# buffer.net
KiCad netlist of a schematic drawn in Altium Designer
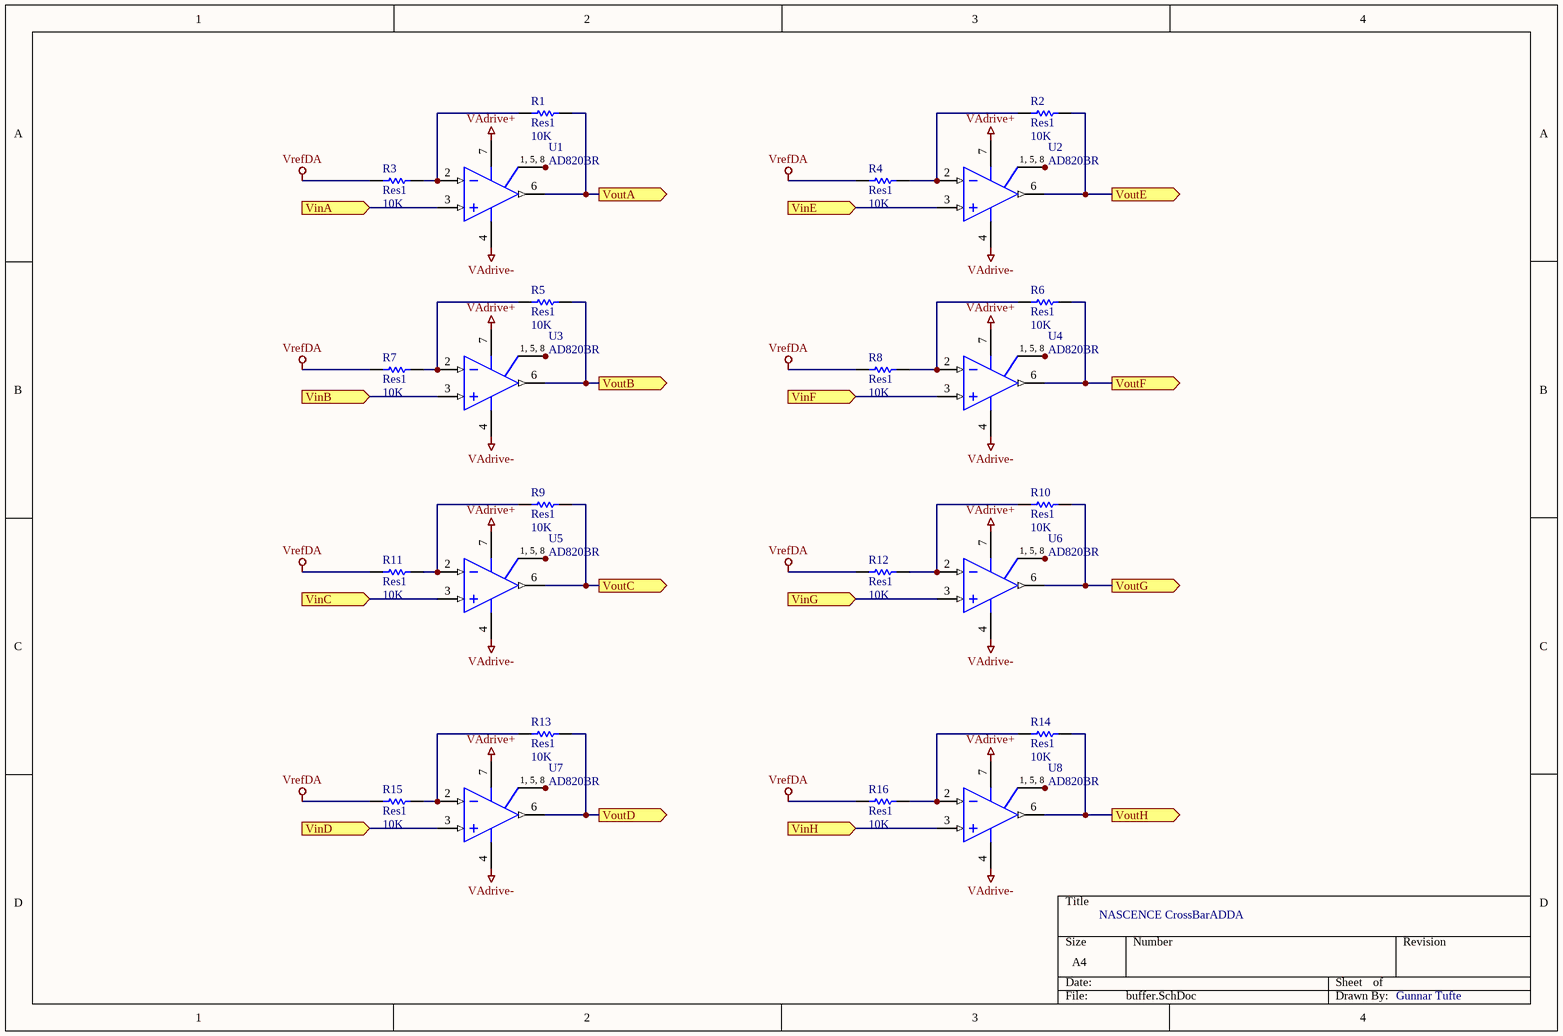
[diagram p0: buffer.SchDoc]

(export (version "E")
  (design (tool "Eeschema 10.0.6"))
  (components
    (comp (ref "R1")
      (value "Res1")
      (footprint "AXIAL-0.3")
      (description "Resistor")
      (fields (field (name "ALTIUM_VALUE") "10K") (field (name "PUBLISHER") "Altium Limited"))
      (libsource (lib "Miscellaneous Devices") (part "Res1"))
    )
    (comp (ref "R2")
      (value "Res1")
      (footprint "AXIAL-0.3")
      (description "Resistor")
      (fields (field (name "ALTIUM_VALUE") "10K") (field (name "PUBLISHER") "Altium Limited"))
      (libsource (lib "Miscellaneous Devices") (part "Res1"))
    )
    (comp (ref "R3")
      (value "Res1")
      (footprint "AXIAL-0.3")
      (description "Resistor")
      (fields (field (name "ALTIUM_VALUE") "10K") (field (name "PUBLISHER") "Altium Limited"))
      (libsource (lib "Miscellaneous Devices") (part "Res1"))
    )
    (comp (ref "R4")
      (value "Res1")
      (footprint "AXIAL-0.3")
      (description "Resistor")
      (fields (field (name "ALTIUM_VALUE") "10K") (field (name "PUBLISHER") "Altium Limited"))
      (libsource (lib "Miscellaneous Devices") (part "Res1"))
    )
    (comp (ref "R5")
      (value "Res1")
      (footprint "AXIAL-0.3")
      (description "Resistor")
      (fields (field (name "ALTIUM_VALUE") "10K") (field (name "PUBLISHER") "Altium Limited"))
      (libsource (lib "Miscellaneous Devices") (part "Res1"))
    )
    (comp (ref "R6")
      (value "Res1")
      (footprint "AXIAL-0.3")
      (description "Resistor")
      (fields (field (name "ALTIUM_VALUE") "10K") (field (name "PUBLISHER") "Altium Limited"))
      (libsource (lib "Miscellaneous Devices") (part "Res1"))
    )
    (comp (ref "R7")
      (value "Res1")
      (footprint "AXIAL-0.3")
      (description "Resistor")
      (fields (field (name "ALTIUM_VALUE") "10K") (field (name "PUBLISHER") "Altium Limited"))
      (libsource (lib "Miscellaneous Devices") (part "Res1"))
    )
    (comp (ref "R8")
      (value "Res1")
      (footprint "AXIAL-0.3")
      (description "Resistor")
      (fields (field (name "ALTIUM_VALUE") "10K") (field (name "PUBLISHER") "Altium Limited"))
      (libsource (lib "Miscellaneous Devices") (part "Res1"))
    )
    (comp (ref "R9")
      (value "Res1")
      (footprint "AXIAL-0.3")
      (description "Resistor")
      (fields (field (name "ALTIUM_VALUE") "10K") (field (name "PUBLISHER") "Altium Limited"))
      (libsource (lib "Miscellaneous Devices") (part "Res1"))
    )
    (comp (ref "R10")
      (value "Res1")
      (footprint "AXIAL-0.3")
      (description "Resistor")
      (fields (field (name "ALTIUM_VALUE") "10K") (field (name "PUBLISHER") "Altium Limited"))
      (libsource (lib "Miscellaneous Devices") (part "Res1"))
    )
    (comp (ref "R11")
      (value "Res1")
      (footprint "AXIAL-0.3")
      (description "Resistor")
      (fields (field (name "ALTIUM_VALUE") "10K") (field (name "PUBLISHER") "Altium Limited"))
      (libsource (lib "Miscellaneous Devices") (part "Res1"))
    )
    (comp (ref "R12")
      (value "Res1")
      (footprint "AXIAL-0.3")
      (description "Resistor")
      (fields (field (name "ALTIUM_VALUE") "10K") (field (name "PUBLISHER") "Altium Limited"))
      (libsource (lib "Miscellaneous Devices") (part "Res1"))
    )
    (comp (ref "R13")
      (value "Res1")
      (footprint "AXIAL-0.3")
      (description "Resistor")
      (fields (field (name "ALTIUM_VALUE") "10K") (field (name "PUBLISHER") "Altium Limited"))
      (libsource (lib "Miscellaneous Devices") (part "Res1"))
    )
    (comp (ref "R14")
      (value "Res1")
      (footprint "AXIAL-0.3")
      (description "Resistor")
      (fields (field (name "ALTIUM_VALUE") "10K") (field (name "PUBLISHER") "Altium Limited"))
      (libsource (lib "Miscellaneous Devices") (part "Res1"))
    )
    (comp (ref "R15")
      (value "Res1")
      (footprint "AXIAL-0.3")
      (description "Resistor")
      (fields (field (name "ALTIUM_VALUE") "10K") (field (name "PUBLISHER") "Altium Limited"))
      (libsource (lib "Miscellaneous Devices") (part "Res1"))
    )
    (comp (ref "R16")
      (value "Res1")
      (footprint "AXIAL-0.3")
      (description "Resistor")
      (fields (field (name "ALTIUM_VALUE") "10K") (field (name "PUBLISHER") "Altium Limited"))
      (libsource (lib "Miscellaneous Devices") (part "Res1"))
    )
    (comp (ref "U1")
      (value "AD820BR")
      (footprint "R-8D_N")
      (description "Single-Supply, Rail-to-Rail Low-Power FET-Input Operational Amplifier")
      (fields (field (name "PUBLISHER") "Altium Limited"))
      (libsource (lib "AD Operational Amplifier") (part "AD820BR"))
    )
    (comp (ref "U2")
      (value "AD820BR")
      (footprint "R-8D_N")
      (description "Single-Supply, Rail-to-Rail Low-Power FET-Input Operational Amplifier")
      (fields (field (name "PUBLISHER") "Altium Limited"))
      (libsource (lib "AD Operational Amplifier") (part "AD820BR"))
    )
    (comp (ref "U3")
      (value "AD820BR")
      (footprint "R-8D_N")
      (description "Single-Supply, Rail-to-Rail Low-Power FET-Input Operational Amplifier")
      (fields (field (name "PUBLISHER") "Altium Limited"))
      (libsource (lib "AD Operational Amplifier") (part "AD820BR"))
    )
    (comp (ref "U4")
      (value "AD820BR")
      (footprint "R-8D_N")
      (description "Single-Supply, Rail-to-Rail Low-Power FET-Input Operational Amplifier")
      (fields (field (name "PUBLISHER") "Altium Limited"))
      (libsource (lib "AD Operational Amplifier") (part "AD820BR"))
    )
    (comp (ref "U5")
      (value "AD820BR")
      (footprint "R-8D_N")
      (description "Single-Supply, Rail-to-Rail Low-Power FET-Input Operational Amplifier")
      (fields (field (name "PUBLISHER") "Altium Limited"))
      (libsource (lib "AD Operational Amplifier") (part "AD820BR"))
    )
    (comp (ref "U6")
      (value "AD820BR")
      (footprint "R-8D_N")
      (description "Single-Supply, Rail-to-Rail Low-Power FET-Input Operational Amplifier")
      (fields (field (name "PUBLISHER") "Altium Limited"))
      (libsource (lib "AD Operational Amplifier") (part "AD820BR"))
    )
    (comp (ref "U7")
      (value "AD820BR")
      (footprint "R-8D_N")
      (description "Single-Supply, Rail-to-Rail Low-Power FET-Input Operational Amplifier")
      (fields (field (name "PUBLISHER") "Altium Limited"))
      (libsource (lib "AD Operational Amplifier") (part "AD820BR"))
    )
    (comp (ref "U8")
      (value "AD820BR")
      (footprint "R-8D_N")
      (description "Single-Supply, Rail-to-Rail Low-Power FET-Input Operational Amplifier")
      (fields (field (name "PUBLISHER") "Altium Limited"))
      (libsource (lib "AD Operational Amplifier") (part "AD820BR"))
    )
  )
  (nets
    (net (code "1") (name "/VinA") (class "Default")
      (node (ref "U1") (pin "3") (pinfunction "IN+_3") (pintype "input"))
    )
    (net (code "2") (name "/VinB") (class "Default")
      (node (ref "U3") (pin "3") (pinfunction "IN+_3") (pintype "input"))
    )
    (net (code "3") (name "/VinC") (class "Default")
      (node (ref "U5") (pin "3") (pinfunction "IN+_3") (pintype "input"))
    )
    (net (code "4") (name "/VinD") (class "Default")
      (node (ref "U7") (pin "3") (pinfunction "IN+_3") (pintype "input"))
    )
    (net (code "5") (name "/VinE") (class "Default")
      (node (ref "U2") (pin "3") (pinfunction "IN+_3") (pintype "input"))
    )
    (net (code "6") (name "/VinF") (class "Default")
      (node (ref "U4") (pin "3") (pinfunction "IN+_3") (pintype "input"))
    )
    (net (code "7") (name "/VinG") (class "Default")
      (node (ref "U6") (pin "3") (pinfunction "IN+_3") (pintype "input"))
    )
    (net (code "8") (name "/VinH") (class "Default")
      (node (ref "U8") (pin "3") (pinfunction "IN+_3") (pintype "input"))
    )
    (net (code "9") (name "/VoutA") (class "Default")
      (node (ref "R1") (pin "2") (pinfunction "2_2") (pintype "passive"))
      (node (ref "U1") (pin "6") (pinfunction "OUT_6") (pintype "output"))
    )
    (net (code "10") (name "/VoutB") (class "Default")
      (node (ref "R5") (pin "2") (pinfunction "2_2") (pintype "passive"))
      (node (ref "U3") (pin "6") (pinfunction "OUT_6") (pintype "output"))
    )
    (net (code "11") (name "/VoutC") (class "Default")
      (node (ref "R9") (pin "2") (pinfunction "2_2") (pintype "passive"))
      (node (ref "U5") (pin "6") (pinfunction "OUT_6") (pintype "output"))
    )
    (net (code "12") (name "/VoutD") (class "Default")
      (node (ref "R13") (pin "2") (pinfunction "2_2") (pintype "passive"))
      (node (ref "U7") (pin "6") (pinfunction "OUT_6") (pintype "output"))
    )
    (net (code "13") (name "/VoutE") (class "Default")
      (node (ref "R2") (pin "2") (pinfunction "2_2") (pintype "passive"))
      (node (ref "U2") (pin "6") (pinfunction "OUT_6") (pintype "output"))
    )
    (net (code "14") (name "/VoutF") (class "Default")
      (node (ref "R6") (pin "2") (pinfunction "2_2") (pintype "passive"))
      (node (ref "U4") (pin "6") (pinfunction "OUT_6") (pintype "output"))
    )
    (net (code "15") (name "/VoutG") (class "Default")
      (node (ref "R10") (pin "2") (pinfunction "2_2") (pintype "passive"))
      (node (ref "U6") (pin "6") (pinfunction "OUT_6") (pintype "output"))
    )
    (net (code "16") (name "/VoutH") (class "Default")
      (node (ref "R14") (pin "2") (pinfunction "2_2") (pintype "passive"))
      (node (ref "U8") (pin "6") (pinfunction "OUT_6") (pintype "output"))
    )
    (net (code "17") (name "Net-(U1-IN-)") (class "Default")
      (node (ref "R1") (pin "1") (pinfunction "1_1") (pintype "passive"))
      (node (ref "R3") (pin "2") (pinfunction "2_2") (pintype "passive"))
      (node (ref "U1") (pin "2") (pinfunction "IN-_2") (pintype "input"))
    )
    (net (code "18") (name "Net-(U1-NC-Pad1)") (class "Default")
      (node (ref "U1") (pin "1") (pinfunction "NC_1") (pintype "passive"))
      (node (ref "U1") (pin "5") (pinfunction "NC_5") (pintype "passive"))
      (node (ref "U1") (pin "8") (pinfunction "NC_8") (pintype "passive"))
    )
    (net (code "19") (name "Net-(U2-IN-)") (class "Default")
      (node (ref "R2") (pin "1") (pinfunction "1_1") (pintype "passive"))
      (node (ref "R4") (pin "2") (pinfunction "2_2") (pintype "passive"))
      (node (ref "U2") (pin "2") (pinfunction "IN-_2") (pintype "input"))
    )
    (net (code "20") (name "Net-(U2-NC-Pad1)") (class "Default")
      (node (ref "U2") (pin "1") (pinfunction "NC_1") (pintype "passive"))
      (node (ref "U2") (pin "5") (pinfunction "NC_5") (pintype "passive"))
      (node (ref "U2") (pin "8") (pinfunction "NC_8") (pintype "passive"))
    )
    (net (code "21") (name "Net-(U3-IN-)") (class "Default")
      (node (ref "R5") (pin "1") (pinfunction "1_1") (pintype "passive"))
      (node (ref "R7") (pin "2") (pinfunction "2_2") (pintype "passive"))
      (node (ref "U3") (pin "2") (pinfunction "IN-_2") (pintype "input"))
    )
    (net (code "22") (name "Net-(U3-NC-Pad1)") (class "Default")
      (node (ref "U3") (pin "1") (pinfunction "NC_1") (pintype "passive"))
      (node (ref "U3") (pin "5") (pinfunction "NC_5") (pintype "passive"))
      (node (ref "U3") (pin "8") (pinfunction "NC_8") (pintype "passive"))
    )
    (net (code "23") (name "Net-(U4-IN-)") (class "Default")
      (node (ref "R6") (pin "1") (pinfunction "1_1") (pintype "passive"))
      (node (ref "R8") (pin "2") (pinfunction "2_2") (pintype "passive"))
      (node (ref "U4") (pin "2") (pinfunction "IN-_2") (pintype "input"))
    )
    (net (code "24") (name "Net-(U4-NC-Pad1)") (class "Default")
      (node (ref "U4") (pin "1") (pinfunction "NC_1") (pintype "passive"))
      (node (ref "U4") (pin "5") (pinfunction "NC_5") (pintype "passive"))
      (node (ref "U4") (pin "8") (pinfunction "NC_8") (pintype "passive"))
    )
    (net (code "25") (name "Net-(U5-IN-)") (class "Default")
      (node (ref "R11") (pin "2") (pinfunction "2_2") (pintype "passive"))
      (node (ref "R9") (pin "1") (pinfunction "1_1") (pintype "passive"))
      (node (ref "U5") (pin "2") (pinfunction "IN-_2") (pintype "input"))
    )
    (net (code "26") (name "Net-(U5-NC-Pad1)") (class "Default")
      (node (ref "U5") (pin "1") (pinfunction "NC_1") (pintype "passive"))
      (node (ref "U5") (pin "5") (pinfunction "NC_5") (pintype "passive"))
      (node (ref "U5") (pin "8") (pinfunction "NC_8") (pintype "passive"))
    )
    (net (code "27") (name "Net-(U6-IN-)") (class "Default")
      (node (ref "R10") (pin "1") (pinfunction "1_1") (pintype "passive"))
      (node (ref "R12") (pin "2") (pinfunction "2_2") (pintype "passive"))
      (node (ref "U6") (pin "2") (pinfunction "IN-_2") (pintype "input"))
    )
    (net (code "28") (name "Net-(U6-NC-Pad1)") (class "Default")
      (node (ref "U6") (pin "1") (pinfunction "NC_1") (pintype "passive"))
      (node (ref "U6") (pin "5") (pinfunction "NC_5") (pintype "passive"))
      (node (ref "U6") (pin "8") (pinfunction "NC_8") (pintype "passive"))
    )
    (net (code "29") (name "Net-(U7-IN-)") (class "Default")
      (node (ref "R13") (pin "1") (pinfunction "1_1") (pintype "passive"))
      (node (ref "R15") (pin "2") (pinfunction "2_2") (pintype "passive"))
      (node (ref "U7") (pin "2") (pinfunction "IN-_2") (pintype "input"))
    )
    (net (code "30") (name "Net-(U7-NC-Pad1)") (class "Default")
      (node (ref "U7") (pin "1") (pinfunction "NC_1") (pintype "passive"))
      (node (ref "U7") (pin "5") (pinfunction "NC_5") (pintype "passive"))
      (node (ref "U7") (pin "8") (pinfunction "NC_8") (pintype "passive"))
    )
    (net (code "31") (name "Net-(U8-IN-)") (class "Default")
      (node (ref "R14") (pin "1") (pinfunction "1_1") (pintype "passive"))
      (node (ref "R16") (pin "2") (pinfunction "2_2") (pintype "passive"))
      (node (ref "U8") (pin "2") (pinfunction "IN-_2") (pintype "input"))
    )
    (net (code "32") (name "Net-(U8-NC-Pad1)") (class "Default")
      (node (ref "U8") (pin "1") (pinfunction "NC_1") (pintype "passive"))
      (node (ref "U8") (pin "5") (pinfunction "NC_5") (pintype "passive"))
      (node (ref "U8") (pin "8") (pinfunction "NC_8") (pintype "passive"))
    )
    (net (code "33") (name "VAdrive+") (class "Default")
      (node (ref "U1") (pin "7") (pinfunction "V+_7") (pintype "power_in"))
      (node (ref "U2") (pin "7") (pinfunction "V+_7") (pintype "power_in"))
      (node (ref "U3") (pin "7") (pinfunction "V+_7") (pintype "power_in"))
      (node (ref "U4") (pin "7") (pinfunction "V+_7") (pintype "power_in"))
      (node (ref "U5") (pin "7") (pinfunction "V+_7") (pintype "power_in"))
      (node (ref "U6") (pin "7") (pinfunction "V+_7") (pintype "power_in"))
      (node (ref "U7") (pin "7") (pinfunction "V+_7") (pintype "power_in"))
      (node (ref "U8") (pin "7") (pinfunction "V+_7") (pintype "power_in"))
    )
    (net (code "34") (name "VAdrive-") (class "Default")
      (node (ref "U1") (pin "4") (pinfunction "V-_4") (pintype "power_in"))
      (node (ref "U2") (pin "4") (pinfunction "V-_4") (pintype "power_in"))
      (node (ref "U3") (pin "4") (pinfunction "V-_4") (pintype "power_in"))
      (node (ref "U4") (pin "4") (pinfunction "V-_4") (pintype "power_in"))
      (node (ref "U5") (pin "4") (pinfunction "V-_4") (pintype "power_in"))
      (node (ref "U6") (pin "4") (pinfunction "V-_4") (pintype "power_in"))
      (node (ref "U7") (pin "4") (pinfunction "V-_4") (pintype "power_in"))
      (node (ref "U8") (pin "4") (pinfunction "V-_4") (pintype "power_in"))
    )
    (net (code "35") (name "VrefDA") (class "Default")
      (node (ref "R11") (pin "1") (pinfunction "1_1") (pintype "passive"))
      (node (ref "R12") (pin "1") (pinfunction "1_1") (pintype "passive"))
      (node (ref "R15") (pin "1") (pinfunction "1_1") (pintype "passive"))
      (node (ref "R16") (pin "1") (pinfunction "1_1") (pintype "passive"))
      (node (ref "R3") (pin "1") (pinfunction "1_1") (pintype "passive"))
      (node (ref "R4") (pin "1") (pinfunction "1_1") (pintype "passive"))
      (node (ref "R7") (pin "1") (pinfunction "1_1") (pintype "passive"))
      (node (ref "R8") (pin "1") (pinfunction "1_1") (pintype "passive"))
    )
  )
)
